# Diode_Board.net
KiCad netlist of a schematic drawn in Altium Designer
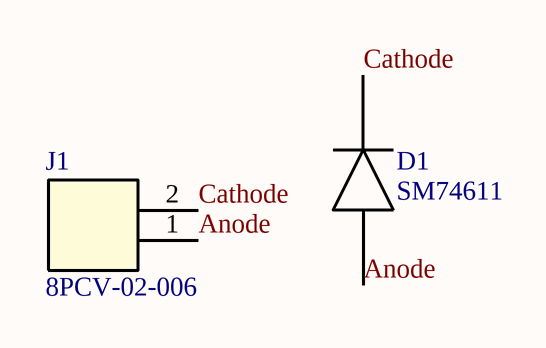
[diagram p0: Diode Board.SchDoc]

(export (version "E")
  (design (tool "Eeschema 10.0.6"))
  (components
    (comp (ref "D1")
      (value "SM74611")
      (footprint "SM74611 Smart Bypass Diode - TI")
      (description "SM74611 Smart Bypass Diode - TI")
      (libsource (lib "SM74611 Smart Bypass Diode - TI") (part "SM74611 Smart Bypass Diode - TI"))
    )
    (comp (ref "J1")
      (value "8PCV-02-006")
      (footprint "CON2_1X2_P438R_B")
      (description "Imported")
      (libsource (lib "CONN Barrier Strip 2Circular 0.438in") (part "8PCV-02-006"))
    )
  )
  (nets
    (net (code "1") (name "/Anode") (class "Default")
      (node (ref "D1") (pin "1") (pintype "passive"))
      (node (ref "D1") (pin "3") (pintype "passive"))
      (node (ref "J1") (pin "1") (pinfunction "1_1") (pintype "passive"))
    )
    (net (code "2") (name "/Cathode") (class "Default")
      (node (ref "D1") (pin "4") (pintype "passive"))
      (node (ref "J1") (pin "2") (pinfunction "2_2") (pintype "passive"))
    )
  )
)
